# bristol_longshot_development.net
KiCad netlist of a schematic drawn in EAGLE
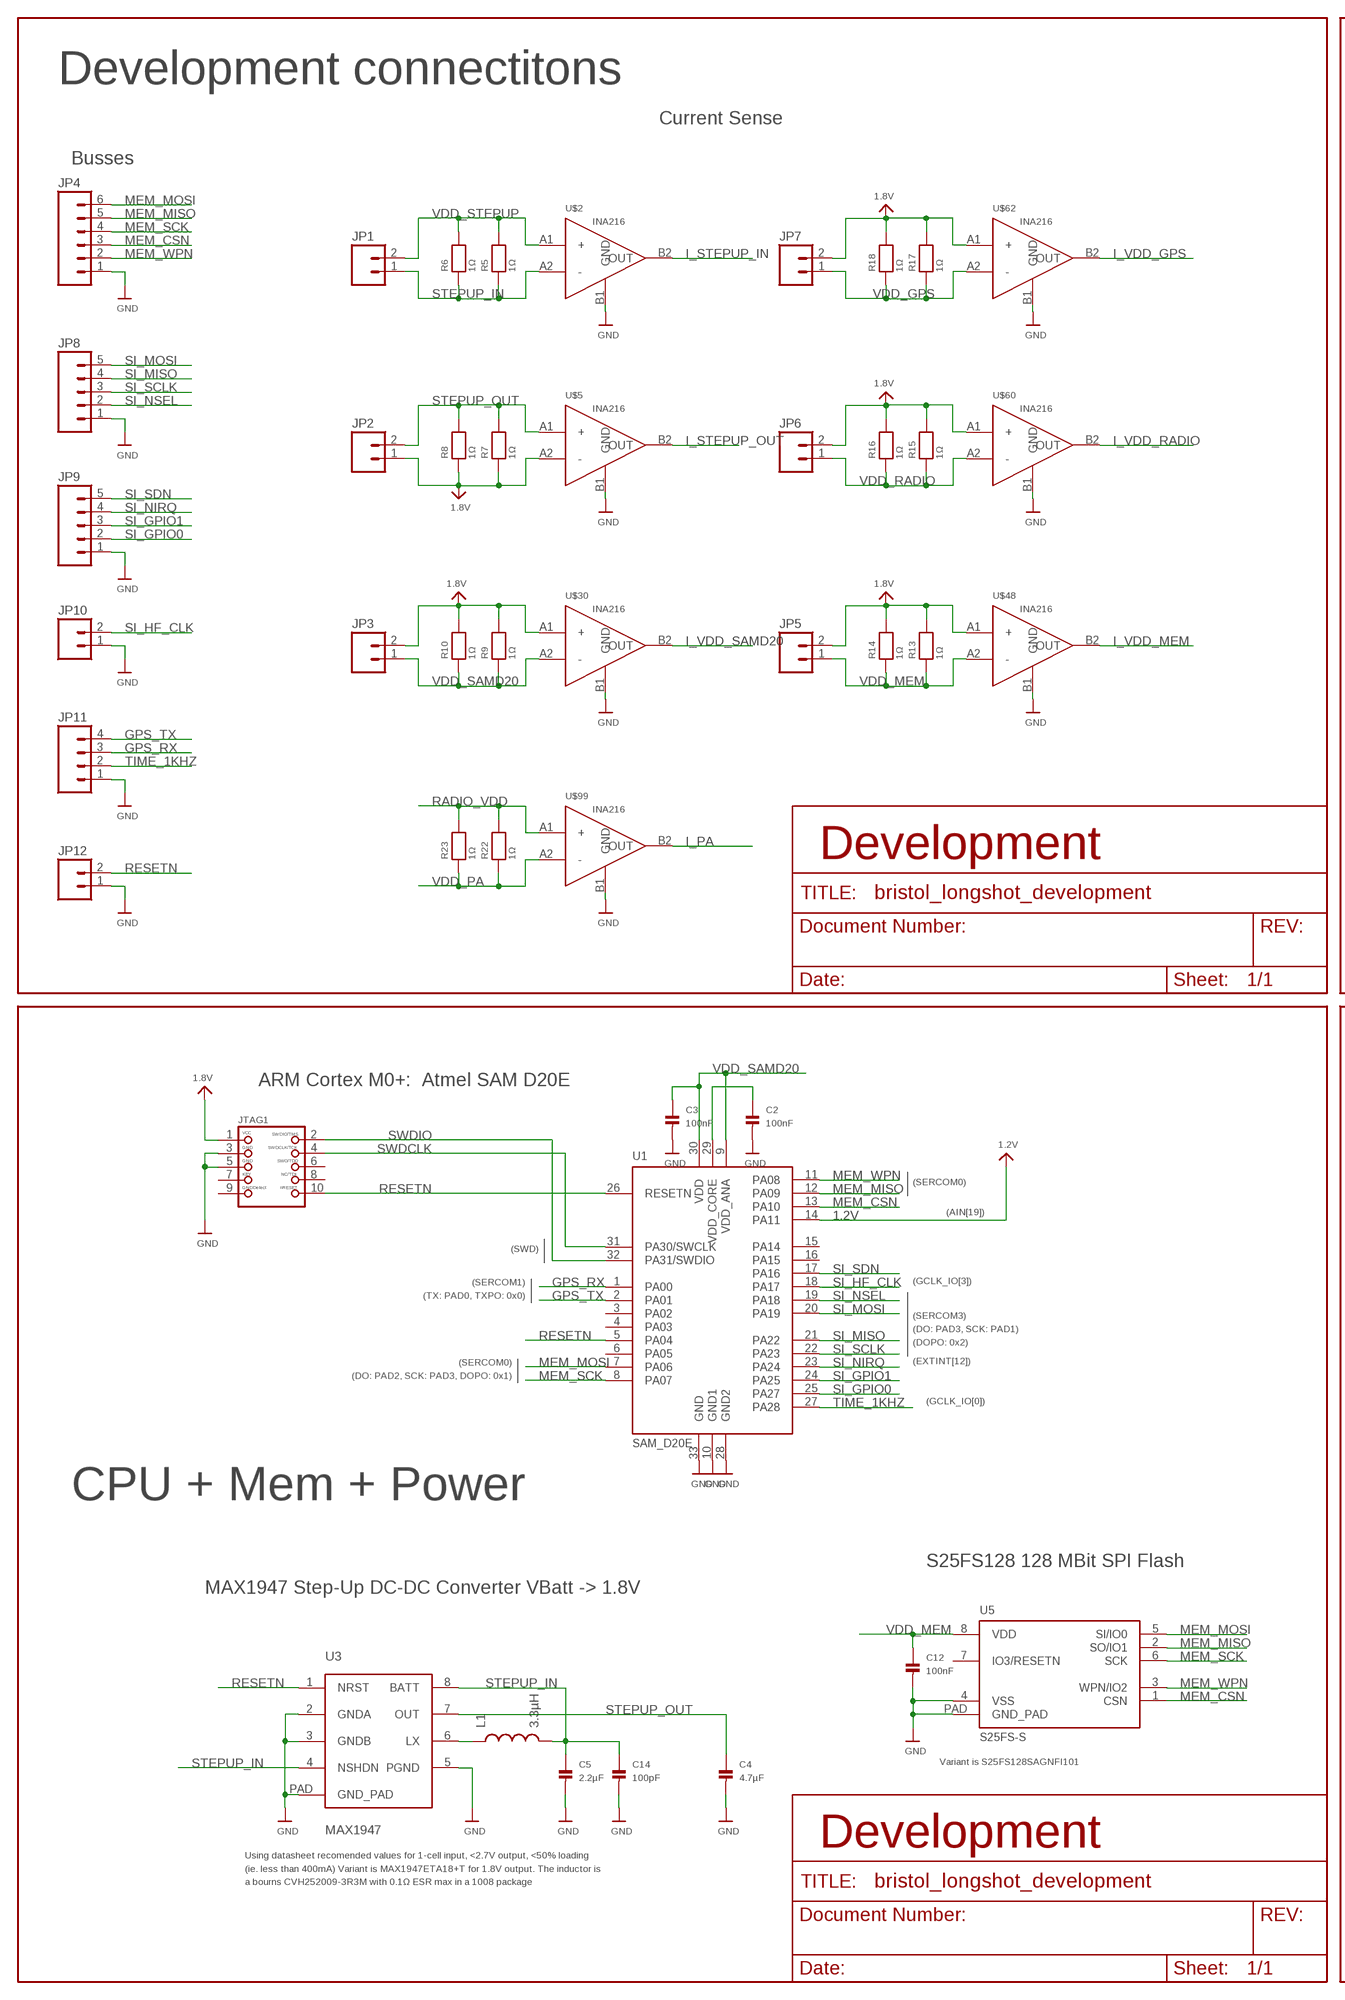
[diagram p0: schematic, sheet 1, part 1 of 2]
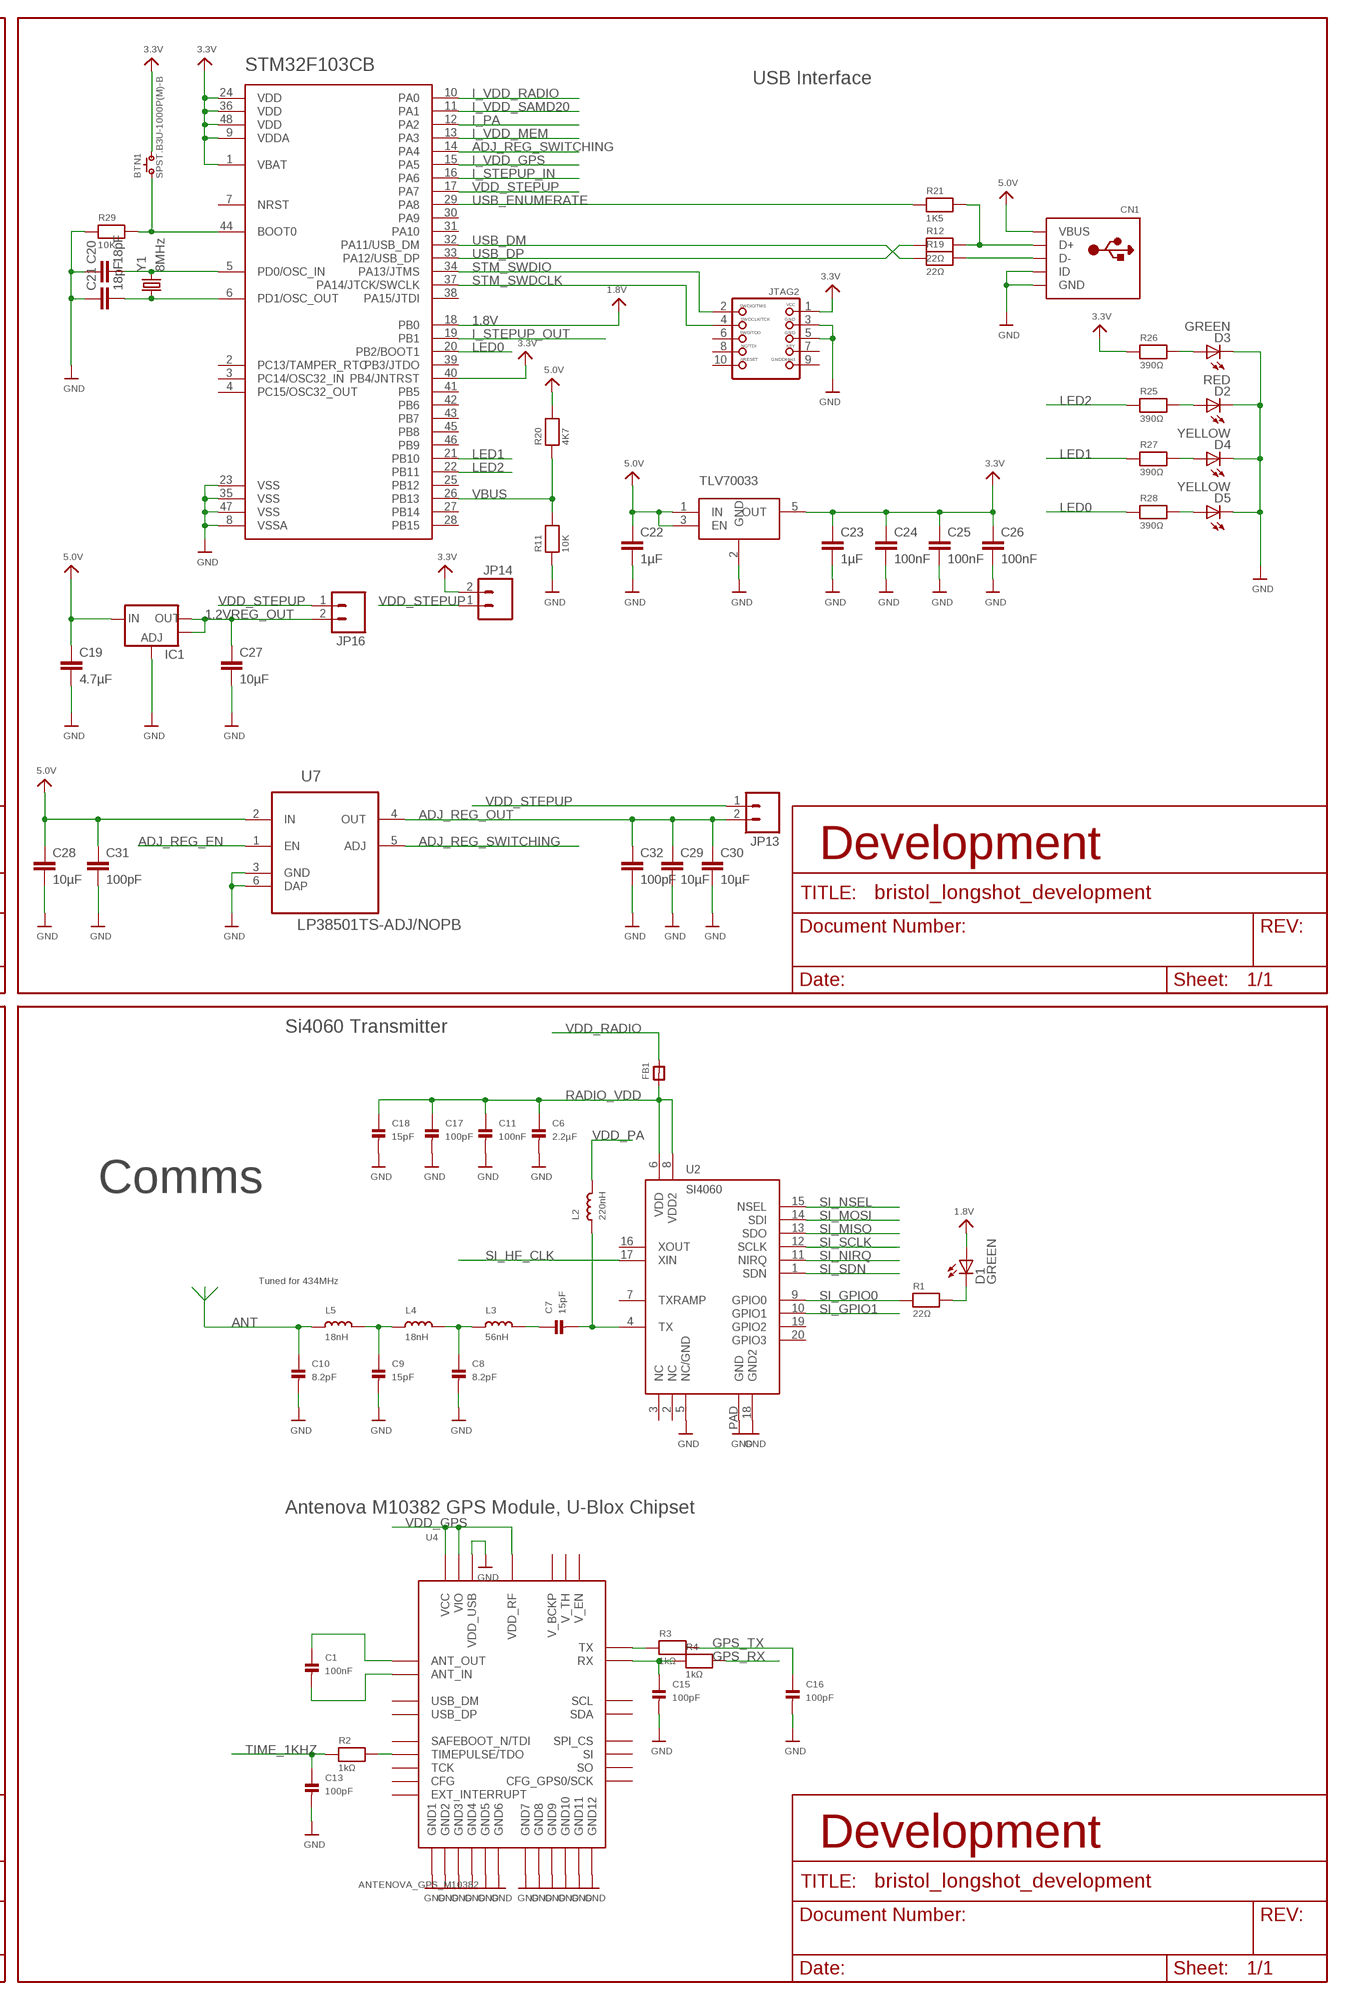
[diagram p1: schematic, sheet 1, part 2 of 2]

(export (version "E")
  (design (tool "Eeschema 10.0.6"))
  (components
    (comp (ref "BTN1")
      (value "SPST.B3U-1000P(M)-B")
      (footprint "eagle-import:B3U-1000P(M)-B")
      (libsource (lib "eagle-import") (part "SPST.B3U-1000P(M)-B"))
    )
    (comp (ref "C1")
      (value "100nF")
      (footprint "eagle-import:_0402")
      (libsource (lib "eagle-import") (part "CAP_CERAMIC_0402"))
    )
    (comp (ref "C2")
      (value "100nF")
      (footprint "eagle-import:_0402")
      (libsource (lib "eagle-import") (part "CAP_CERAMIC_0402"))
    )
    (comp (ref "C3")
      (value "100nF")
      (footprint "eagle-import:_0402")
      (libsource (lib "eagle-import") (part "CAP_CERAMIC_0402"))
    )
    (comp (ref "C4")
      (value "4.7µF")
      (footprint "eagle-import:_0402")
      (libsource (lib "eagle-import") (part "CAP_CERAMIC_0402"))
    )
    (comp (ref "C5")
      (value "2.2µF")
      (footprint "eagle-import:_0402")
      (libsource (lib "eagle-import") (part "CAP_CERAMIC_0402"))
    )
    (comp (ref "C6")
      (value "2.2µF")
      (footprint "eagle-import:_0402")
      (libsource (lib "eagle-import") (part "CAP_CERAMIC_0402"))
    )
    (comp (ref "C7")
      (value "15pF")
      (footprint "eagle-import:_0402")
      (libsource (lib "eagle-import") (part "CAP_CERAMIC_0402"))
    )
    (comp (ref "C8")
      (value "8.2pF")
      (footprint "eagle-import:_0402")
      (libsource (lib "eagle-import") (part "CAP_CERAMIC_0402"))
    )
    (comp (ref "C9")
      (value "15pF")
      (footprint "eagle-import:_0402")
      (libsource (lib "eagle-import") (part "CAP_CERAMIC_0402"))
    )
    (comp (ref "C10")
      (value "8.2pF")
      (footprint "eagle-import:_0402")
      (libsource (lib "eagle-import") (part "CAP_CERAMIC_0402"))
    )
    (comp (ref "C11")
      (value "100nF")
      (footprint "eagle-import:_0402")
      (libsource (lib "eagle-import") (part "CAP_CERAMIC_0402"))
    )
    (comp (ref "C12")
      (value "100nF")
      (footprint "eagle-import:_0402")
      (libsource (lib "eagle-import") (part "CAP_CERAMIC_0402"))
    )
    (comp (ref "C13")
      (value "100pF")
      (footprint "eagle-import:_0402")
      (libsource (lib "eagle-import") (part "CAP_CERAMIC_0402"))
    )
    (comp (ref "C14")
      (value "100pF")
      (footprint "eagle-import:_0402")
      (libsource (lib "eagle-import") (part "CAP_CERAMIC_0402"))
    )
    (comp (ref "C15")
      (value "100pF")
      (footprint "eagle-import:_0402")
      (libsource (lib "eagle-import") (part "CAP_CERAMIC_0402"))
    )
    (comp (ref "C16")
      (value "100pF")
      (footprint "eagle-import:_0402")
      (libsource (lib "eagle-import") (part "CAP_CERAMIC_0402"))
    )
    (comp (ref "C17")
      (value "100pF")
      (footprint "eagle-import:_0402")
      (libsource (lib "eagle-import") (part "CAP_CERAMIC_0402"))
    )
    (comp (ref "C18")
      (value "15pF")
      (footprint "eagle-import:_0402")
      (libsource (lib "eagle-import") (part "CAP_CERAMIC_0402"))
    )
    (comp (ref "C19")
      (value "4.7µF")
      (footprint "eagle-import:C0603K")
      (libsource (lib "eagle-import") (part "C-EUC0603K"))
    )
    (comp (ref "C20")
      (value "18pF")
      (footprint "eagle-import:C0603K")
      (libsource (lib "eagle-import") (part "C-EUC0603K"))
    )
    (comp (ref "C21")
      (value "18pF")
      (footprint "eagle-import:C0603K")
      (libsource (lib "eagle-import") (part "C-EUC0603K"))
    )
    (comp (ref "C22")
      (value "1µF")
      (footprint "eagle-import:C0603K")
      (libsource (lib "eagle-import") (part "C-EUC0603K"))
    )
    (comp (ref "C23")
      (value "1µF")
      (footprint "eagle-import:C0603K")
      (libsource (lib "eagle-import") (part "C-EUC0603K"))
    )
    (comp (ref "C24")
      (value "100nF")
      (footprint "eagle-import:C0603K")
      (libsource (lib "eagle-import") (part "C-EUC0603K"))
    )
    (comp (ref "C25")
      (value "100nF")
      (footprint "eagle-import:C0603K")
      (libsource (lib "eagle-import") (part "C-EUC0603K"))
    )
    (comp (ref "C26")
      (value "100nF")
      (footprint "eagle-import:C0603K")
      (libsource (lib "eagle-import") (part "C-EUC0603K"))
    )
    (comp (ref "C27")
      (value "10µF")
      (footprint "eagle-import:C0603K")
      (libsource (lib "eagle-import") (part "C-EUC0603K"))
    )
    (comp (ref "C28")
      (value "10µF")
      (footprint "eagle-import:C0603K")
      (libsource (lib "eagle-import") (part "C-EUC0603K"))
    )
    (comp (ref "C29")
      (value "10µF")
      (footprint "eagle-import:C0603K")
      (libsource (lib "eagle-import") (part "C-EUC0603K"))
    )
    (comp (ref "C30")
      (value "10µF")
      (footprint "eagle-import:C0603K")
      (libsource (lib "eagle-import") (part "C-EUC0603K"))
    )
    (comp (ref "C31")
      (value "100pF")
      (footprint "eagle-import:C0603K")
      (libsource (lib "eagle-import") (part "C-EUC0603K"))
    )
    (comp (ref "C32")
      (value "100pF")
      (footprint "eagle-import:C0603K")
      (libsource (lib "eagle-import") (part "C-EUC0603K"))
    )
    (comp (ref "CN1")
      (value "USBMINIB")
      (footprint "eagle-import:USB-MINIB")
      (libsource (lib "eagle-import") (part "USBMINIB"))
    )
    (comp (ref "D1")
      (value "GREEN")
      (footprint "eagle-import:CHIPLED_0603")
      (libsource (lib "eagle-import") (part "LEDCHIPLED_0603"))
    )
    (comp (ref "D2")
      (value "RED")
      (footprint "eagle-import:CHIPLED_0603")
      (libsource (lib "eagle-import") (part "LEDCHIPLED_0603"))
    )
    (comp (ref "D3")
      (value "GREEN")
      (footprint "eagle-import:CHIPLED_0603")
      (libsource (lib "eagle-import") (part "LEDCHIPLED_0603"))
    )
    (comp (ref "D4")
      (value "YELLOW")
      (footprint "eagle-import:CHIPLED_0603")
      (libsource (lib "eagle-import") (part "LEDCHIPLED_0603"))
    )
    (comp (ref "D5")
      (value "YELLOW")
      (footprint "eagle-import:CHIPLED_0603")
      (libsource (lib "eagle-import") (part "LEDCHIPLED_0603"))
    )
    (comp (ref "FB1")
      (value "FERRITE_0402")
      (footprint "eagle-import:_0402")
      (libsource (lib "eagle-import") (part "FERRITE_0402"))
    )
    (comp (ref "IC1")
      (value "V_REG_LM1117SOT223")
      (footprint "eagle-import:SOT223")
      (libsource (lib "eagle-import") (part "V_REG_LM1117SOT223"))
    )
    (comp (ref "IC3")
      (value "TLV70033DCK")
      (footprint "eagle-import:SC70-5L")
      (libsource (lib "eagle-import") (part "TLV700DCK"))
    )
    (comp (ref "JP1")
      (value "M02LOCK")
      (footprint "eagle-import:1X02_LOCK")
      (libsource (lib "eagle-import") (part "M02LOCK"))
    )
    (comp (ref "JP2")
      (value "M02LOCK")
      (footprint "eagle-import:1X02_LOCK")
      (libsource (lib "eagle-import") (part "M02LOCK"))
    )
    (comp (ref "JP3")
      (value "M02LOCK")
      (footprint "eagle-import:1X02_LOCK")
      (libsource (lib "eagle-import") (part "M02LOCK"))
    )
    (comp (ref "JP4")
      (value "M06LOCK")
      (footprint "eagle-import:1X06_LOCK")
      (libsource (lib "eagle-import") (part "M06LOCK"))
    )
    (comp (ref "JP5")
      (value "M02LOCK")
      (footprint "eagle-import:1X02_LOCK")
      (libsource (lib "eagle-import") (part "M02LOCK"))
    )
    (comp (ref "JP6")
      (value "M02LOCK")
      (footprint "eagle-import:1X02_LOCK")
      (libsource (lib "eagle-import") (part "M02LOCK"))
    )
    (comp (ref "JP7")
      (value "M02LOCK")
      (footprint "eagle-import:1X02_LOCK")
      (libsource (lib "eagle-import") (part "M02LOCK"))
    )
    (comp (ref "JP8")
      (value "M05LOCK")
      (footprint "eagle-import:1X05_LOCK")
      (libsource (lib "eagle-import") (part "M05LOCK"))
    )
    (comp (ref "JP9")
      (value "M05LOCK")
      (footprint "eagle-import:1X05_LOCK")
      (libsource (lib "eagle-import") (part "M05LOCK"))
    )
    (comp (ref "JP10")
      (value "M02LOCK")
      (footprint "eagle-import:1X02_LOCK")
      (libsource (lib "eagle-import") (part "M02LOCK"))
    )
    (comp (ref "JP11")
      (value "M04LOCK")
      (footprint "eagle-import:1X04_LOCK")
      (libsource (lib "eagle-import") (part "M04LOCK"))
    )
    (comp (ref "JP12")
      (value "M02LOCK")
      (footprint "eagle-import:1X02_LOCK")
      (libsource (lib "eagle-import") (part "M02LOCK"))
    )
    (comp (ref "JP13")
      (value "M02LOCK")
      (footprint "eagle-import:1X02_LOCK")
      (libsource (lib "eagle-import") (part "M02LOCK"))
    )
    (comp (ref "JP14")
      (value "M02LOCK")
      (footprint "eagle-import:1X02_LOCK")
      (libsource (lib "eagle-import") (part "M02LOCK"))
    )
    (comp (ref "JP16")
      (value "M02LOCK")
      (footprint "eagle-import:1X02_LOCK")
      (libsource (lib "eagle-import") (part "M02LOCK"))
    )
    (comp (ref "JTAG1")
      (value "JTAG-CORTEXM3SMT")
      (footprint "eagle-import:2X05_1.27MM_SMT")
      (libsource (lib "eagle-import") (part "JTAG-CORTEXM3SMT"))
    )
    (comp (ref "JTAG2")
      (value "JTAG-CORTEXM3SMT")
      (footprint "eagle-import:2X05_1.27MM_SMT")
      (libsource (lib "eagle-import") (part "JTAG-CORTEXM3SMT"))
    )
    (comp (ref "L1")
      (value "3.3µH")
      (footprint "eagle-import:1007")
      (libsource (lib "eagle-import") (part "INDUCTOR1007"))
    )
    (comp (ref "L2")
      (value "220nH")
      (footprint "eagle-import:_0402")
      (libsource (lib "eagle-import") (part "INDUCTOR_0402"))
    )
    (comp (ref "L3")
      (value "56nH")
      (footprint "eagle-import:_0402")
      (libsource (lib "eagle-import") (part "INDUCTOR_0402"))
    )
    (comp (ref "L4")
      (value "18nH")
      (footprint "eagle-import:_0402")
      (libsource (lib "eagle-import") (part "INDUCTOR_0402"))
    )
    (comp (ref "L5")
      (value "18nH")
      (footprint "eagle-import:_0402")
      (libsource (lib "eagle-import") (part "INDUCTOR_0402"))
    )
    (comp (ref "R1")
      (value "22Ω")
      (footprint "eagle-import:_0402")
      (libsource (lib "eagle-import") (part "RESISTOR_0402"))
    )
    (comp (ref "R2")
      (value "1kΩ")
      (footprint "eagle-import:_0402")
      (libsource (lib "eagle-import") (part "RESISTOR_0402"))
    )
    (comp (ref "R3")
      (value "1kΩ")
      (footprint "eagle-import:_0402")
      (libsource (lib "eagle-import") (part "RESISTOR_0402"))
    )
    (comp (ref "R4")
      (value "1kΩ")
      (footprint "eagle-import:_0402")
      (libsource (lib "eagle-import") (part "RESISTOR_0402"))
    )
    (comp (ref "R5")
      (value "1Ω")
      (footprint "eagle-import:_0402")
      (libsource (lib "eagle-import") (part "RESISTOR_0402"))
    )
    (comp (ref "R6")
      (value "1Ω")
      (footprint "eagle-import:_0402")
      (libsource (lib "eagle-import") (part "RESISTOR_0402"))
    )
    (comp (ref "R7")
      (value "1Ω")
      (footprint "eagle-import:_0402")
      (libsource (lib "eagle-import") (part "RESISTOR_0402"))
    )
    (comp (ref "R8")
      (value "1Ω")
      (footprint "eagle-import:_0402")
      (libsource (lib "eagle-import") (part "RESISTOR_0402"))
    )
    (comp (ref "R9")
      (value "1Ω")
      (footprint "eagle-import:_0402")
      (libsource (lib "eagle-import") (part "RESISTOR_0402"))
    )
    (comp (ref "R10")
      (value "1Ω")
      (footprint "eagle-import:_0402")
      (libsource (lib "eagle-import") (part "RESISTOR_0402"))
    )
    (comp (ref "R11")
      (value "10K")
      (footprint "eagle-import:0603-MINI")
      (libsource (lib "eagle-import") (part "RESISTOR0603MINI"))
    )
    (comp (ref "R12")
      (value "22Ω")
      (footprint "eagle-import:0603-MINI")
      (libsource (lib "eagle-import") (part "RESISTOR0603MINI"))
    )
    (comp (ref "R13")
      (value "1Ω")
      (footprint "eagle-import:_0402")
      (libsource (lib "eagle-import") (part "RESISTOR_0402"))
    )
    (comp (ref "R14")
      (value "1Ω")
      (footprint "eagle-import:_0402")
      (libsource (lib "eagle-import") (part "RESISTOR_0402"))
    )
    (comp (ref "R15")
      (value "1Ω")
      (footprint "eagle-import:_0402")
      (libsource (lib "eagle-import") (part "RESISTOR_0402"))
    )
    (comp (ref "R16")
      (value "1Ω")
      (footprint "eagle-import:_0402")
      (libsource (lib "eagle-import") (part "RESISTOR_0402"))
    )
    (comp (ref "R17")
      (value "1Ω")
      (footprint "eagle-import:_0402")
      (libsource (lib "eagle-import") (part "RESISTOR_0402"))
    )
    (comp (ref "R18")
      (value "1Ω")
      (footprint "eagle-import:_0402")
      (libsource (lib "eagle-import") (part "RESISTOR_0402"))
    )
    (comp (ref "R19")
      (value "22Ω")
      (footprint "eagle-import:0603-MINI")
      (libsource (lib "eagle-import") (part "RESISTOR0603MINI"))
    )
    (comp (ref "R20")
      (value "4K7")
      (footprint "eagle-import:0603-MINI")
      (libsource (lib "eagle-import") (part "RESISTOR0603MINI"))
    )
    (comp (ref "R21")
      (value "1K5")
      (footprint "eagle-import:0603-MINI")
      (libsource (lib "eagle-import") (part "RESISTOR0603MINI"))
    )
    (comp (ref "R22")
      (value "1Ω")
      (footprint "eagle-import:_0402")
      (libsource (lib "eagle-import") (part "RESISTOR_0402"))
    )
    (comp (ref "R23")
      (value "1Ω")
      (footprint "eagle-import:_0402")
      (libsource (lib "eagle-import") (part "RESISTOR_0402"))
    )
    (comp (ref "R25")
      (value "390Ω")
      (footprint "eagle-import:0603-MINI")
      (libsource (lib "eagle-import") (part "RESISTOR0603MINI"))
    )
    (comp (ref "R26")
      (value "390Ω")
      (footprint "eagle-import:0603-MINI")
      (libsource (lib "eagle-import") (part "RESISTOR0603MINI"))
    )
    (comp (ref "R27")
      (value "390Ω")
      (footprint "eagle-import:0603-MINI")
      (libsource (lib "eagle-import") (part "RESISTOR0603MINI"))
    )
    (comp (ref "R28")
      (value "390Ω")
      (footprint "eagle-import:0603-MINI")
      (libsource (lib "eagle-import") (part "RESISTOR0603MINI"))
    )
    (comp (ref "R29")
      (value "10K")
      (footprint "eagle-import:0603-MINI")
      (libsource (lib "eagle-import") (part "RESISTOR0603MINI"))
    )
    (comp (ref "U$2")
      (value "INA216")
      (footprint "eagle-import:WCSP-4")
      (libsource (lib "eagle-import") (part "INA216"))
    )
    (comp (ref "U$5")
      (value "INA216")
      (footprint "eagle-import:WCSP-4")
      (libsource (lib "eagle-import") (part "INA216"))
    )
    (comp (ref "U$30")
      (value "INA216")
      (footprint "eagle-import:WCSP-4")
      (libsource (lib "eagle-import") (part "INA216"))
    )
    (comp (ref "U$48")
      (value "INA216")
      (footprint "eagle-import:WCSP-4")
      (libsource (lib "eagle-import") (part "INA216"))
    )
    (comp (ref "U$60")
      (value "INA216")
      (footprint "eagle-import:WCSP-4")
      (libsource (lib "eagle-import") (part "INA216"))
    )
    (comp (ref "U$62")
      (value "INA216")
      (footprint "eagle-import:WCSP-4")
      (libsource (lib "eagle-import") (part "INA216"))
    )
    (comp (ref "U$99")
      (value "INA216")
      (footprint "eagle-import:WCSP-4")
      (libsource (lib "eagle-import") (part "INA216"))
    )
    (comp (ref "U1")
      (value "SAM_D20E")
      (footprint "eagle-import:QFN32_5MM")
      (libsource (lib "eagle-import") (part "SAM_D20E"))
    )
    (comp (ref "U2")
      (value "SI4060")
      (footprint "eagle-import:QFN20")
      (libsource (lib "eagle-import") (part "SI4060"))
    )
    (comp (ref "U3")
      (value "MAX1947")
      (footprint "eagle-import:TDFN8")
      (libsource (lib "eagle-import") (part "MAX1947"))
    )
    (comp (ref "U4")
      (value "ANTENOVA_GPS_M10382")
      (footprint "eagle-import:ANTENOVA_GPS_M10382")
      (libsource (lib "eagle-import") (part "ANTENOVA_GPS_M10382"))
    )
    (comp (ref "U5")
      (value "S25FS-S")
      (footprint "eagle-import:WSON8")
      (libsource (lib "eagle-import") (part "S25FS-S"))
    )
    (comp (ref "U6")
      (value "STM32F_48PIN")
      (footprint "eagle-import:TQFP48")
      (libsource (lib "eagle-import") (part "STM32F_48PIN"))
    )
    (comp (ref "U7")
      (value "LP38501TS-ADJ/NOPB")
      (footprint "eagle-import:TO170P1435X457-6N")
      (libsource (lib "eagle-import") (part "LP38501TS-ADJ/NOPB"))
    )
    (comp (ref "Y1")
      (value "8MHz")
      (footprint "eagle-import:CRYSTAL-SMD-5X3")
      (libsource (lib "eagle-import") (part "CRYSTAL5X3"))
    )
  )
  (nets
    (net (code "1") (name "/1.2VREG_OUT") (class "Default")
      (node (ref "C27") (pin "1") (pinfunction "1_1") (pintype "passive"))
      (node (ref "IC1") (pin "2") (pinfunction "OUT_2") (pintype "output"))
      (node (ref "IC1") (pin "4") (pinfunction "OUT_4") (pintype "output"))
      (node (ref "JP16") (pin "2") (pinfunction "2_2") (pintype "passive"))
    )
    (net (code "2") (name "/ADJ_REG_EN") (class "Default")
      (node (ref "U7") (pin "1") (pinfunction "EN_1") (pintype "input"))
    )
    (net (code "3") (name "/ADJ_REG_OUT") (class "Default")
      (node (ref "C29") (pin "1") (pinfunction "1_1") (pintype "passive"))
      (node (ref "C30") (pin "1") (pinfunction "1_1") (pintype "passive"))
      (node (ref "C32") (pin "1") (pinfunction "1_1") (pintype "passive"))
      (node (ref "JP13") (pin "2") (pinfunction "2_2") (pintype "passive"))
      (node (ref "U7") (pin "4") (pinfunction "OUT_4") (pintype "output"))
    )
    (net (code "4") (name "/ADJ_REG_SWITCHING") (class "Default")
      (node (ref "U6") (pin "14") (pinfunction "PA4_14") (pintype "bidirectional"))
      (node (ref "U7") (pin "5") (pinfunction "ADJ_5") (pintype "input"))
    )
    (net (code "5") (name "/ANT") (class "Default")
      (node (ref "C10") (pin "1") (pinfunction "P$1_1") (pintype "passive"))
      (node (ref "L5") (pin "1") (pinfunction "1_1") (pintype "passive"))
    )
    (net (code "6") (name "/GPS_RX") (class "Default")
      (node (ref "JP11") (pin "3") (pinfunction "3_3") (pintype "passive"))
      (node (ref "R4") (pin "2") (pinfunction "2_2") (pintype "passive"))
      (node (ref "U1") (pin "1") (pinfunction "PA00_1") (pintype "bidirectional"))
    )
    (net (code "7") (name "/GPS_TX") (class "Default")
      (node (ref "C16") (pin "1") (pinfunction "P$1_1") (pintype "passive"))
      (node (ref "JP11") (pin "4") (pinfunction "4_4") (pintype "passive"))
      (node (ref "R3") (pin "2") (pinfunction "2_2") (pintype "passive"))
      (node (ref "U1") (pin "2") (pinfunction "PA01_2") (pintype "bidirectional"))
    )
    (net (code "8") (name "/I_PA") (class "Default")
      (node (ref "U$99") (pin "B2") (pinfunction "OUT_B2") (pintype "bidirectional"))
      (node (ref "U6") (pin "12") (pinfunction "PA2_12") (pintype "bidirectional"))
    )
    (net (code "9") (name "/I_STEPUP_IN") (class "Default")
      (node (ref "U$2") (pin "B2") (pinfunction "OUT_B2") (pintype "bidirectional"))
      (node (ref "U6") (pin "16") (pinfunction "PA6_16") (pintype "bidirectional"))
    )
    (net (code "10") (name "/I_STEPUP_OUT") (class "Default")
      (node (ref "U$5") (pin "B2") (pinfunction "OUT_B2") (pintype "bidirectional"))
      (node (ref "U6") (pin "19") (pinfunction "PB1_19") (pintype "bidirectional"))
    )
    (net (code "11") (name "/I_VDD_GPS") (class "Default")
      (node (ref "U$62") (pin "B2") (pinfunction "OUT_B2") (pintype "bidirectional"))
      (node (ref "U6") (pin "15") (pinfunction "PA5_15") (pintype "bidirectional"))
    )
    (net (code "12") (name "/I_VDD_MEM") (class "Default")
      (node (ref "U$48") (pin "B2") (pinfunction "OUT_B2") (pintype "bidirectional"))
      (node (ref "U6") (pin "13") (pinfunction "PA3_13") (pintype "bidirectional"))
    )
    (net (code "13") (name "/I_VDD_RADIO") (class "Default")
      (node (ref "U$60") (pin "B2") (pinfunction "OUT_B2") (pintype "bidirectional"))
      (node (ref "U6") (pin "10") (pinfunction "PA0_10") (pintype "bidirectional"))
    )
    (net (code "14") (name "/I_VDD_SAMD20") (class "Default")
      (node (ref "U$30") (pin "B2") (pinfunction "OUT_B2") (pintype "bidirectional"))
      (node (ref "U6") (pin "11") (pinfunction "PA1_11") (pintype "bidirectional"))
    )
    (net (code "15") (name "/LED0") (class "Default")
      (node (ref "R28") (pin "1") (pinfunction "1_1") (pintype "passive"))
      (node (ref "U6") (pin "20") (pinfunction "PB2/BOOT1_20") (pintype "bidirectional"))
    )
    (net (code "16") (name "/LED1") (class "Default")
      (node (ref "R27") (pin "1") (pinfunction "1_1") (pintype "passive"))
      (node (ref "U6") (pin "21") (pinfunction "PB10_21") (pintype "bidirectional"))
    )
    (net (code "17") (name "/LED2") (class "Default")
      (node (ref "R25") (pin "1") (pinfunction "1_1") (pintype "passive"))
      (node (ref "U6") (pin "22") (pinfunction "PB11_22") (pintype "bidirectional"))
    )
    (net (code "18") (name "/MEM_CSN") (class "Default")
      (node (ref "JP4") (pin "3") (pinfunction "3_3") (pintype "passive"))
      (node (ref "U1") (pin "13") (pinfunction "PA10_13") (pintype "bidirectional"))
      (node (ref "U5") (pin "1") (pinfunction "CSN_1") (pintype "input"))
    )
    (net (code "19") (name "/MEM_MISO") (class "Default")
      (node (ref "JP4") (pin "5") (pinfunction "5_5") (pintype "passive"))
      (node (ref "U1") (pin "12") (pinfunction "PA09_12") (pintype "bidirectional"))
      (node (ref "U5") (pin "2") (pinfunction "SO/IO1_2") (pintype "output"))
    )
    (net (code "20") (name "/MEM_MOSI") (class "Default")
      (node (ref "JP4") (pin "6") (pinfunction "6_6") (pintype "passive"))
      (node (ref "U1") (pin "7") (pinfunction "PA06_7") (pintype "bidirectional"))
      (node (ref "U5") (pin "5") (pinfunction "SI/IO0_5") (pintype "bidirectional"))
    )
    (net (code "21") (name "/MEM_SCK") (class "Default")
      (node (ref "JP4") (pin "4") (pinfunction "4_4") (pintype "passive"))
      (node (ref "U1") (pin "8") (pinfunction "PA07_8") (pintype "bidirectional"))
      (node (ref "U5") (pin "6") (pinfunction "SCK_6") (pintype "input"))
    )
    (net (code "22") (name "/MEM_WPN") (class "Default")
      (node (ref "JP4") (pin "2") (pinfunction "2_2") (pintype "passive"))
      (node (ref "U1") (pin "11") (pinfunction "PA08_11") (pintype "bidirectional"))
      (node (ref "U5") (pin "3") (pinfunction "WPN/IO2_3") (pintype "output"))
    )
    (net (code "23") (name "/RADIO_VDD") (class "Default")
      (node (ref "C11") (pin "1") (pinfunction "P$1_1") (pintype "passive"))
      (node (ref "C17") (pin "1") (pinfunction "P$1_1") (pintype "passive"))
      (node (ref "C18") (pin "1") (pinfunction "P$1_1") (pintype "passive"))
      (node (ref "C6") (pin "1") (pinfunction "P$1_1") (pintype "passive"))
      (node (ref "FB1") (pin "1") (pinfunction "P$1_1") (pintype "passive"))
      (node (ref "R22") (pin "2") (pinfunction "2_2") (pintype "passive"))
      (node (ref "R23") (pin "2") (pinfunction "2_2") (pintype "passive"))
      (node (ref "U$99") (pin "A1") (pinfunction "+_A1") (pintype "bidirectional"))
      (node (ref "U2") (pin "6") (pinfunction "VDD_6") (pintype "power_in"))
      (node (ref "U2") (pin "8") (pinfunction "VDD2_8") (pintype "power_in"))
    )
    (net (code "24") (name "/RESETN") (class "Default")
      (node (ref "JP12") (pin "2") (pinfunction "2_2") (pintype "passive"))
      (node (ref "JTAG1") (pin "10") (pinfunction "10_10") (pintype "passive"))
      (node (ref "U1") (pin "26") (pinfunction "RESETN_26") (pintype "input"))
      (node (ref "U1") (pin "5") (pinfunction "PA04_5") (pintype "bidirectional"))
      (node (ref "U3") (pin "1") (pinfunction "NRST_1") (pintype "bidirectional"))
    )
    (net (code "25") (name "/SI_GPIO0") (class "Default")
      (node (ref "JP9") (pin "2") (pinfunction "2_2") (pintype "passive"))
      (node (ref "R1") (pin "1") (pinfunction "1_1") (pintype "passive"))
      (node (ref "U1") (pin "25") (pinfunction "PA27_25") (pintype "bidirectional"))
      (node (ref "U2") (pin "9") (pinfunction "GPIO0_9") (pintype "bidirectional"))
    )
    (net (code "26") (name "/SI_GPIO1") (class "Default")
      (node (ref "JP9") (pin "3") (pinfunction "3_3") (pintype "passive"))
      (node (ref "U1") (pin "24") (pinfunction "PA25_24") (pintype "bidirectional"))
      (node (ref "U2") (pin "10") (pinfunction "GPIO1_10") (pintype "bidirectional"))
    )
    (net (code "27") (name "/SI_HF_CLK") (class "Default")
      (node (ref "JP10") (pin "2") (pinfunction "2_2") (pintype "passive"))
      (node (ref "U1") (pin "18") (pinfunction "PA17_18") (pintype "bidirectional"))
      (node (ref "U2") (pin "17") (pinfunction "XIN_17") (pintype "input"))
    )
    (net (code "28") (name "/SI_MISO") (class "Default")
      (node (ref "JP8") (pin "4") (pinfunction "4_4") (pintype "passive"))
      (node (ref "U1") (pin "21") (pinfunction "PA22_21") (pintype "bidirectional"))
      (node (ref "U2") (pin "13") (pinfunction "SDO_13") (pintype "output"))
    )
    (net (code "29") (name "/SI_MOSI") (class "Default")
      (node (ref "JP8") (pin "5") (pinfunction "5_5") (pintype "passive"))
      (node (ref "U1") (pin "20") (pinfunction "PA19_20") (pintype "bidirectional"))
      (node (ref "U2") (pin "14") (pinfunction "SDI_14") (pintype "bidirectional"))
    )
    (net (code "30") (name "/SI_NIRQ") (class "Default")
      (node (ref "JP9") (pin "4") (pinfunction "4_4") (pintype "passive"))
      (node (ref "U1") (pin "23") (pinfunction "PA24_23") (pintype "bidirectional"))
      (node (ref "U2") (pin "11") (pinfunction "NIRQ_11") (pintype "output"))
    )
    (net (code "31") (name "/SI_NSEL") (class "Default")
      (node (ref "JP8") (pin "2") (pinfunction "2_2") (pintype "passive"))
      (node (ref "U1") (pin "19") (pinfunction "PA18_19") (pintype "bidirectional"))
      (node (ref "U2") (pin "15") (pinfunction "NSEL_15") (pintype "input"))
    )
    (net (code "32") (name "/SI_SCLK") (class "Default")
      (node (ref "JP8") (pin "3") (pinfunction "3_3") (pintype "passive"))
      (node (ref "U1") (pin "22") (pinfunction "PA23_22") (pintype "bidirectional"))
      (node (ref "U2") (pin "12") (pinfunction "SCLK_12") (pintype "input"))
    )
    (net (code "33") (name "/SI_SDN") (class "Default")
      (node (ref "JP9") (pin "5") (pinfunction "5_5") (pintype "passive"))
      (node (ref "U1") (pin "17") (pinfunction "PA16_17") (pintype "bidirectional"))
      (node (ref "U2") (pin "1") (pinfunction "SDN_1") (pintype "input"))
    )
    (net (code "34") (name "/STEPUP_IN") (class "Default")
      (node (ref "C14") (pin "1") (pinfunction "P$1_1") (pintype "passive"))
      (node (ref "C5") (pin "1") (pinfunction "P$1_1") (pintype "passive"))
      (node (ref "JP1") (pin "1") (pinfunction "1_1") (pintype "passive"))
      (node (ref "L1") (pin "2") (pinfunction "2_2") (pintype "passive"))
      (node (ref "R5") (pin "1") (pinfunction "1_1") (pintype "passive"))
      (node (ref "R6") (pin "1") (pinfunction "1_1") (pintype "passive"))
      (node (ref "U$2") (pin "A2") (pinfunction "-_A2") (pintype "bidirectional"))
      (node (ref "U3") (pin "4") (pinfunction "NSHDN_4") (pintype "bidirectional"))
      (node (ref "U3") (pin "8") (pinfunction "BATT_8") (pintype "bidirectional"))
    )
    (net (code "35") (name "/STEPUP_OUT") (class "Default")
      (node (ref "C4") (pin "1") (pinfunction "P$1_1") (pintype "passive"))
      (node (ref "JP2") (pin "2") (pinfunction "2_2") (pintype "passive"))
      (node (ref "R7") (pin "2") (pinfunction "2_2") (pintype "passive"))
      (node (ref "R8") (pin "2") (pinfunction "2_2") (pintype "passive"))
      (node (ref "U$5") (pin "A1") (pinfunction "+_A1") (pintype "bidirectional"))
      (node (ref "U3") (pin "7") (pinfunction "OUT_7") (pintype "bidirectional"))
    )
    (net (code "36") (name "/STM_SWDCLK") (class "Default")
      (node (ref "JTAG2") (pin "4") (pinfunction "4_4") (pintype "passive"))
      (node (ref "U6") (pin "37") (pinfunction "PA14/JTCK/SWCLK_37") (pintype "bidirectional"))
    )
    (net (code "37") (name "/STM_SWDIO") (class "Default")
      (node (ref "JTAG2") (pin "2") (pinfunction "2_2") (pintype "passive"))
      (node (ref "U6") (pin "34") (pinfunction "PA13/JTMS_34") (pintype "bidirectional"))
    )
    (net (code "38") (name "/SWDCLK") (class "Default")
      (node (ref "JTAG1") (pin "4") (pinfunction "4_4") (pintype "passive"))
      (node (ref "U1") (pin "31") (pinfunction "PA30/SWCLK_31") (pintype "bidirectional"))
    )
    (net (code "39") (name "/SWDIO") (class "Default")
      (node (ref "JTAG1") (pin "2") (pinfunction "2_2") (pintype "passive"))
      (node (ref "U1") (pin "32") (pinfunction "PA31/SWDIO_32") (pintype "bidirectional"))
    )
    (net (code "40") (name "/TIME_1KHZ") (class "Default")
      (node (ref "C13") (pin "1") (pinfunction "P$1_1") (pintype "passive"))
      (node (ref "JP11") (pin "2") (pinfunction "2_2") (pintype "passive"))
      (node (ref "R2") (pin "1") (pinfunction "1_1") (pintype "passive"))
      (node (ref "U1") (pin "27") (pinfunction "PA28_27") (pintype "bidirectional"))
    )
    (net (code "41") (name "/USB_DM") (class "Default")
      (node (ref "R19") (pin "1") (pinfunction "1_1") (pintype "passive"))
      (node (ref "U6") (pin "32") (pinfunction "PA11/USB_DM_32") (pintype "bidirectional"))
    )
    (net (code "42") (name "/USB_DP") (class "Default")
      (node (ref "R12") (pin "1") (pinfunction "1_1") (pintype "passive"))
      (node (ref "U6") (pin "33") (pinfunction "PA12/USB_DP_33") (pintype "bidirectional"))
    )
    (net (code "43") (name "/USB_ENUMERATE") (class "Default")
      (node (ref "R21") (pin "1") (pinfunction "1_1") (pintype "passive"))
      (node (ref "U6") (pin "29") (pinfunction "PA8_29") (pintype "bidirectional"))
    )
    (net (code "44") (name "/VBUS") (class "Default")
      (node (ref "R11") (pin "2") (pinfunction "2_2") (pintype "passive"))
      (node (ref "R20") (pin "1") (pinfunction "1_1") (pintype "passive"))
      (node (ref "U6") (pin "26") (pinfunction "PB13_26") (pintype "bidirectional"))
    )
    (net (code "45") (name "/VDD_GPS") (class "Default")
      (node (ref "JP7") (pin "1") (pinfunction "1_1") (pintype "passive"))
      (node (ref "R17") (pin "1") (pinfunction "1_1") (pintype "passive"))
      (node (ref "R18") (pin "1") (pinfunction "1_1") (pintype "passive"))
      (node (ref "U$62") (pin "A2") (pinfunction "-_A2") (pintype "bidirectional"))
      (node (ref "U4") (pin "25_VDD_RF") (pinfunction "VDD_RF_25_VDD_RF") (pintype "power_in"))
      (node (ref "U4") (pin "27_VCC") (pinfunction "VCC_27_VCC") (pintype "power_in"))
      (node (ref "U4") (pin "5_VIO") (pinfunction "VIO_5_VIO") (pintype "bidirectional"))
    )
    (net (code "46") (name "/VDD_MEM") (class "Default")
      (node (ref "C12") (pin "1") (pinfunction "P$1_1") (pintype "passive"))
      (node (ref "JP5") (pin "1") (pinfunction "1_1") (pintype "passive"))
      (node (ref "R13") (pin "1") (pinfunction "1_1") (pintype "passive"))
      (node (ref "R14") (pin "1") (pinfunction "1_1") (pintype "passive"))
      (node (ref "U$48") (pin "A2") (pinfunction "-_A2") (pintype "bidirectional"))
      (node (ref "U5") (pin "8") (pinfunction "VDD_8") (pintype "power_in"))
    )
    (net (code "47") (name "/VDD_PA") (class "Default")
      (node (ref "L2") (pin "2") (pinfunction "2_2") (pintype "passive"))
      (node (ref "R22") (pin "1") (pinfunction "1_1") (pintype "passive"))
      (node (ref "R23") (pin "1") (pinfunction "1_1") (pintype "passive"))
      (node (ref "U$99") (pin "A2") (pinfunction "-_A2") (pintype "bidirectional"))
    )
    (net (code "48") (name "/VDD_RADIO") (class "Default")
      (node (ref "FB1") (pin "2") (pinfunction "P$2_2") (pintype "passive"))
      (node (ref "JP6") (pin "1") (pinfunction "1_1") (pintype "passive"))
      (node (ref "R15") (pin "1") (pinfunction "1_1") (pintype "passive"))
      (node (ref "R16") (pin "1") (pinfunction "1_1") (pintype "passive"))
      (node (ref "U$60") (pin "A2") (pinfunction "-_A2") (pintype "bidirectional"))
    )
    (net (code "49") (name "/VDD_SAMD20") (class "Default")
      (node (ref "C3") (pin "1") (pinfunction "P$1_1") (pintype "passive"))
      (node (ref "JP3") (pin "1") (pinfunction "1_1") (pintype "passive"))
      (node (ref "R10") (pin "1") (pinfunction "1_1") (pintype "passive"))
      (node (ref "R9") (pin "1") (pinfunction "1_1") (pintype "passive"))
      (node (ref "U$30") (pin "A2") (pinfunction "-_A2") (pintype "bidirectional"))
      (node (ref "U1") (pin "30") (pinfunction "VDD_30") (pintype "power_in"))
      (node (ref "U1") (pin "9") (pinfunction "VDD_ANA_9") (pintype "power_in"))
    )
    (net (code "50") (name "/VDD_STEPUP") (class "Default")
      (node (ref "JP1") (pin "2") (pinfunction "2_2") (pintype "passive"))
      (node (ref "JP13") (pin "1") (pinfunction "1_1") (pintype "passive"))
      (node (ref "JP14") (pin "1") (pinfunction "1_1") (pintype "passive"))
      (node (ref "JP16") (pin "1") (pinfunction "1_1") (pintype "passive"))
      (node (ref "R5") (pin "2") (pinfunction "2_2") (pintype "passive"))
      (node (ref "R6") (pin "2") (pinfunction "2_2") (pintype "passive"))
      (node (ref "U$2") (pin "A1") (pinfunction "+_A1") (pintype "bidirectional"))
      (node (ref "U6") (pin "17") (pinfunction "PA7_17") (pintype "bidirectional"))
    )
    (net (code "51") (name "1.2V") (class "Default")
      (node (ref "U1") (pin "14") (pinfunction "PA11_14") (pintype "bidirectional"))
    )
    (net (code "52") (name "1.8V") (class "Default")
      (node (ref "D1") (pin "A") (pinfunction "A_A") (pintype "passive"))
      (node (ref "JP2") (pin "1") (pinfunction "1_1") (pintype "passive"))
      (node (ref "JP3") (pin "2") (pinfunction "2_2") (pintype "passive"))
      (node (ref "JP5") (pin "2") (pinfunction "2_2") (pintype "passive"))
      (node (ref "JP6") (pin "2") (pinfunction "2_2") (pintype "passive"))
      (node (ref "JP7") (pin "2") (pinfunction "2_2") (pintype "passive"))
      (node (ref "JTAG1") (pin "1") (pinfunction "1_1") (pintype "passive"))
      (node (ref "R10") (pin "2") (pinfunction "2_2") (pintype "passive"))
      (node (ref "R13") (pin "2") (pinfunction "2_2") (pintype "passive"))
      (node (ref "R14") (pin "2") (pinfunction "2_2") (pintype "passive"))
      (node (ref "R15") (pin "2") (pinfunction "2_2") (pintype "passive"))
      (node (ref "R16") (pin "2") (pinfunction "2_2") (pintype "passive"))
      (node (ref "R17") (pin "2") (pinfunction "2_2") (pintype "passive"))
      (node (ref "R18") (pin "2") (pinfunction "2_2") (pintype "passive"))
      (node (ref "R7") (pin "1") (pinfunction "1_1") (pintype "passive"))
      (node (ref "R8") (pin "1") (pinfunction "1_1") (pintype "passive"))
      (node (ref "R9") (pin "2") (pinfunction "2_2") (pintype "passive"))
      (node (ref "U$30") (pin "A1") (pinfunction "+_A1") (pintype "bidirectional"))
      (node (ref "U$48") (pin "A1") (pinfunction "+_A1") (pintype "bidirectional"))
      (node (ref "U$5") (pin "A2") (pinfunction "-_A2") (pintype "bidirectional"))
      (node (ref "U$60") (pin "A1") (pinfunction "+_A1") (pintype "bidirectional"))
      (node (ref "U$62") (pin "A1") (pinfunction "+_A1") (pintype "bidirectional"))
      (node (ref "U6") (pin "18") (pinfunction "PB0_18") (pintype "bidirectional"))
    )
    (net (code "53") (name "3.3V") (class "Default")
      (node (ref "BTN1") (pin "2") (pinfunction "2_2") (pintype "bidirectional"))
      (node (ref "C23") (pin "1") (pinfunction "1_1") (pintype "passive"))
      (node (ref "C24") (pin "1") (pinfunction "1_1") (pintype "passive"))
      (node (ref "C25") (pin "1") (pinfunction "1_1") (pintype "passive"))
      (node (ref "C26") (pin "1") (pinfunction "1_1") (pintype "passive"))
      (node (ref "IC3") (pin "5") (pinfunction "OUT_5") (pintype "bidirectional"))
      (node (ref "JP14") (pin "2") (pinfunction "2_2") (pintype "passive"))
      (node (ref "JTAG2") (pin "1") (pinfunction "1_1") (pintype "passive"))
      (node (ref "R26") (pin "1") (pinfunction "1_1") (pintype "passive"))
      (node (ref "U6") (pin "1") (pinfunction "VBAT_1") (pintype "bidirectional"))
      (node (ref "U6") (pin "24") (pinfunction "VDD_24") (pintype "bidirectional"))
      (node (ref "U6") (pin "36") (pinfunction "VDD_36") (pintype "bidirectional"))
      (node (ref "U6") (pin "40") (pinfunction "PB4/JNTRST_40") (pintype "bidirectional"))
      (node (ref "U6") (pin "48") (pinfunction "VDD_48") (pintype "bidirectional"))
      (node (ref "U6") (pin "9") (pinfunction "VDDA_9") (pintype "bidirectional"))
    )
    (net (code "54") (name "5.0V") (class "Default")
      (node (ref "C19") (pin "1") (pinfunction "1_1") (pintype "passive"))
      (node (ref "C22") (pin "1") (pinfunction "1_1") (pintype "passive"))
      (node (ref "C28") (pin "1") (pinfunction "1_1") (pintype "passive"))
      (node (ref "C31") (pin "1") (pinfunction "1_1") (pintype "passive"))
      (node (ref "CN1") (pin "VBUS") (pinfunction "VBUS_VBUS") (pintype "power_in"))
      (node (ref "IC1") (pin "3") (pinfunction "IN_3") (pintype "input"))
      (node (ref "IC3") (pin "1") (pinfunction "IN_1") (pintype "bidirectional"))
      (node (ref "IC3") (pin "3") (pinfunction "EN_3") (pintype "bidirectional"))
      (node (ref "R20") (pin "2") (pinfunction "2_2") (pintype "passive"))
      (node (ref "U7") (pin "2") (pinfunction "IN_2") (pintype "power_in"))
    )
    (net (code "55") (name "GND") (class "Default")
      (node (ref "C10") (pin "2") (pinfunction "P$2_2") (pintype "passive"))
      (node (ref "C11") (pin "2") (pinfunction "P$2_2") (pintype "passive"))
      (node (ref "C12") (pin "2") (pinfunction "P$2_2") (pintype "passive"))
      (node (ref "C13") (pin "2") (pinfunction "P$2_2") (pintype "passive"))
      (node (ref "C14") (pin "2") (pinfunction "P$2_2") (pintype "passive"))
      (node (ref "C15") (pin "2") (pinfunction "P$2_2") (pintype "passive"))
      (node (ref "C16") (pin "2") (pinfunction "P$2_2") (pintype "passive"))
      (node (ref "C17") (pin "2") (pinfunction "P$2_2") (pintype "passive"))
      (node (ref "C18") (pin "2") (pinfunction "P$2_2") (pintype "passive"))
      (node (ref "C19") (pin "2") (pinfunction "2_2") (pintype "passive"))
      (node (ref "C2") (pin "2") (pinfunction "P$2_2") (pintype "passive"))
      (node (ref "C20") (pin "1") (pinfunction "1_1") (pintype "passive"))
      (node (ref "C21") (pin "1") (pinfunction "1_1") (pintype "passive"))
      (node (ref "C22") (pin "2") (pinfunction "2_2") (pintype "passive"))
      (node (ref "C23") (pin "2") (pinfunction "2_2") (pintype "passive"))
      (node (ref "C24") (pin "2") (pinfunction "2_2") (pintype "passive"))
      (node (ref "C25") (pin "2") (pinfunction "2_2") (pintype "passive"))
      (node (ref "C26") (pin "2") (pinfunction "2_2") (pintype "passive"))
      (node (ref "C27") (pin "2") (pinfunction "2_2") (pintype "passive"))
      (node (ref "C28") (pin "2") (pinfunction "2_2") (pintype "passive"))
      (node (ref "C29") (pin "2") (pinfunction "2_2") (pintype "passive"))
      (node (ref "C3") (pin "2") (pinfunction "P$2_2") (pintype "passive"))
      (node (ref "C30") (pin "2") (pinfunction "2_2") (pintype "passive"))
      (node (ref "C31") (pin "2") (pinfunction "2_2") (pintype "passive"))
      (node (ref "C32") (pin "2") (pinfunction "2_2") (pintype "passive"))
      (node (ref "C4") (pin "2") (pinfunction "P$2_2") (pintype "passive"))
      (node (ref "C5") (pin "2") (pinfunction "P$2_2") (pintype "passive"))
      (node (ref "C6") (pin "2") (pinfunction "P$2_2") (pintype "passive"))
      (node (ref "C8") (pin "2") (pinfunction "P$2_2") (pintype "passive"))
      (node (ref "C9") (pin "2") (pinfunction "P$2_2") (pintype "passive"))
      (node (ref "CN1") (pin "GND") (pinfunction "GND_GND") (pintype "power_in"))
      (node (ref "CN1") (pin "ID") (pinfunction "ID_ID") (pintype "bidirectional"))
      (node (ref "D2") (pin "C") (pinfunction "C_C") (pintype "passive"))
      (node (ref "D3") (pin "C") (pinfunction "C_C") (pintype "passive"))
      (node (ref "D4") (pin "C") (pinfunction "C_C") (pintype "passive"))
      (node (ref "D5") (pin "C") (pinfunction "C_C") (pintype "passive"))
      (node (ref "IC1") (pin "1") (pinfunction "ADJ_1") (pintype "input"))
      (node (ref "IC3") (pin "2") (pinfunction "GND_2") (pintype "bidirectional"))
      (node (ref "JP10") (pin "1") (pinfunction "1_1") (pintype "passive"))
      (node (ref "JP11") (pin "1") (pinfunction "1_1") (pintype "passive"))
      (node (ref "JP12") (pin "1") (pinfunction "1_1") (pintype "passive"))
      (node (ref "JP4") (pin "1") (pinfunction "1_1") (pintype "passive"))
      (node (ref "JP8") (pin "1") (pinfunction "1_1") (pintype "passive"))
      (node (ref "JP9") (pin "1") (pinfunction "1_1") (pintype "passive"))
      (node (ref "JTAG1") (pin "3") (pinfunction "3_3") (pintype "passive"))
      (node (ref "JTAG1") (pin "5") (pinfunction "5_5") (pintype "passive"))
      (node (ref "JTAG2") (pin "3") (pinfunction "3_3") (pintype "passive"))
      (node (ref "JTAG2") (pin "5") (pinfunction "5_5") (pintype "passive"))
      (node (ref "R11") (pin "1") (pinfunction "1_1") (pintype "passive"))
      (node (ref "R29") (pin "1") (pinfunction "1_1") (pintype "passive"))
      (node (ref "U$2") (pin "B1") (pinfunction "GND_B1") (pintype "bidirectional"))
      (node (ref "U$30") (pin "B1") (pinfunction "GND_B1") (pintype "bidirectional"))
      (node (ref "U$48") (pin "B1") (pinfunction "GND_B1") (pintype "bidirectional"))
      (node (ref "U$5") (pin "B1") (pinfunction "GND_B1") (pintype "bidirectional"))
      (node (ref "U$60") (pin "B1") (pinfunction "GND_B1") (pintype "bidirectional"))
      (node (ref "U$62") (pin "B1") (pinfunction "GND_B1") (pintype "bidirectional"))
      (node (ref "U$99") (pin "B1") (pinfunction "GND_B1") (pintype "bidirectional"))
      (node (ref "U1") (pin "10") (pinfunction "GND1_10") (pintype "power_in"))
      (node (ref "U1") (pin "28") (pinfunction "GND2_28") (pintype "power_in"))
      (node (ref "U1") (pin "33") (pinfunction "GND_33") (pintype "power_in"))
      (node (ref "U2") (pin "18") (pinfunction "GND2_18") (pintype "power_in"))
      (node (ref "U2") (pin "5") (pinfunction "NC/GND_5") (pintype "bidirectional"))
      (node (ref "U2") (pin "PAD") (pinfunction "GND_PAD") (pintype "power_in"))
      (node (ref "U3") (pin "2") (pinfunction "GNDA_2") (pintype "bidirectional"))
      (node (ref "U3") (pin "3") (pinfunction "GNDB_3") (pintype "bidirectional"))
      (node (ref "U3") (pin "5") (pinfunction "PGND_5") (pintype "bidirectional"))
      (node (ref "U3") (pin "PAD") (pinfunction "GND_PAD_PAD") (pintype "bidirectional"))
      (node (ref "U4") (pin "14_GND") (pinfunction "GND3_14_GND") (pintype "power_in"))
      (node (ref "U4") (pin "17_GND") (pinfunction "GND4_17_GND") (pintype "power_in"))
      (node (ref "U4") (pin "21_GND") (pinfunction "GND5_21_GND") (pintype "bidirectional"))
      (node (ref "U4") (pin "24_GND") (pinfunction "GND6_24_GND") (pintype "bidirectional"))
      (node (ref "U4") (pin "26_GND") (pinfunction "GND7_26_GND") (pintype "power_in"))
      (node (ref "U4") (pin "28_GND") (pinfunction "GND8_28_GND") (pintype "power_in"))
      (node (ref "U4") (pin "2_GND") (pinfunction "GND1_2_GND") (pintype "power_in"))
      (node (ref "U4") (pin "32_VDD_USB") (pinfunction "VDD_USB_32_VDD_USB") (pintype "bidirectional"))
      (node (ref "U4") (pin "33_GND") (pinfunction "GND9_33_GND") (pintype "power_in"))
      (node (ref "U4") (pin "34_GND") (pinfunction "GND10_34_GND") (pintype "power_in"))
      (node (ref "U4") (pin "35_GND") (pinfunction "GND11_35_GND") (pintype "bidirectional"))
      (node (ref "U4") (pin "36_GND") (pinfunction "GND12_36_GND") (pintype "bidirectional"))
      (node (ref "U4") (pin "4_GND") (pinfunction "GND2_4_GND") (pintype "power_in"))
      (node (ref "U5") (pin "4") (pinfunction "VSS_4") (pintype "power_in"))
      (node (ref "U5") (pin "PAD") (pinfunction "GND_PAD_PAD") (pintype "power_in"))
      (node (ref "U6") (pin "23") (pinfunction "VSS_23") (pintype "bidirectional"))
      (node (ref "U6") (pin "35") (pinfunction "VSS_35") (pintype "bidirectional"))
      (node (ref "U6") (pin "47") (pinfunction "VSS_47") (pintype "bidirectional"))
      (node (ref "U6") (pin "8") (pinfunction "VSSA_8") (pintype "bidirectional"))
      (node (ref "U7") (pin "3") (pinfunction "GND_3") (pintype "passive"))
      (node (ref "U7") (pin "6") (pinfunction "DAP_6") (pintype "passive"))
    )
    (net (code "56") (name "Net-(C1-P$1)") (class "Default")
      (node (ref "C1") (pin "1") (pinfunction "P$1_1") (pintype "passive"))
      (node (ref "U4") (pin "3_ANT_OUT") (pinfunction "ANT_OUT_3_ANT_OUT") (pintype "output"))
    )
    (net (code "57") (name "Net-(C1-P$2)") (class "Default")
      (node (ref "C1") (pin "2") (pinfunction "P$2_2") (pintype "passive"))
      (node (ref "U4") (pin "1_ANT_IN") (pinfunction "ANT_IN_1_ANT_IN") (pintype "input"))
    )
    (net (code "58") (name "Net-(C2-P$1)") (class "Default")
      (node (ref "C2") (pin "1") (pinfunction "P$1_1") (pintype "passive"))
      (node (ref "U1") (pin "29") (pinfunction "VDD_CORE_29") (pintype "power_in"))
    )
    (net (code "59") (name "Net-(C7-P$1)") (class "Default")
      (node (ref "C7") (pin "1") (pinfunction "P$1_1") (pintype "passive"))
      (node (ref "L3") (pin "2") (pinfunction "2_2") (pintype "passive"))
    )
    (net (code "60") (name "Net-(C7-P$2)") (class "Default")
      (node (ref "C7") (pin "2") (pinfunction "P$2_2") (pintype "passive"))
      (node (ref "L2") (pin "1") (pinfunction "1_1") (pintype "passive"))
      (node (ref "U2") (pin "4") (pinfunction "TX_4") (pintype "output"))
    )
    (net (code "61") (name "Net-(C8-P$1)") (class "Default")
      (node (ref "C8") (pin "1") (pinfunction "P$1_1") (pintype "passive"))
      (node (ref "L3") (pin "1") (pinfunction "1_1") (pintype "passive"))
      (node (ref "L4") (pin "2") (pinfunction "2_2") (pintype "passive"))
    )
    (net (code "62") (name "Net-(C9-P$1)") (class "Default")
      (node (ref "C9") (pin "1") (pinfunction "P$1_1") (pintype "passive"))
      (node (ref "L4") (pin "1") (pinfunction "1_1") (pintype "passive"))
      (node (ref "L5") (pin "2") (pinfunction "2_2") (pintype "passive"))
    )
    (net (code "63") (name "Net-(C15-P$1)") (class "Default")
      (node (ref "C15") (pin "1") (pinfunction "P$1_1") (pintype "passive"))
      (node (ref "R4") (pin "1") (pinfunction "1_1") (pintype "passive"))
      (node (ref "U4") (pin "13_RX") (pinfunction "RX_13_RX") (pintype "bidirectional"))
    )
    (net (code "64") (name "Net-(CN1-PadD+)") (class "Default")
      (node (ref "CN1") (pin "D+") (pinfunction "D+_D+") (pintype "bidirectional"))
      (node (ref "R12") (pin "2") (pinfunction "2_2") (pintype "passive"))
      (node (ref "R21") (pin "2") (pinfunction "2_2") (pintype "passive"))
    )
    (net (code "65") (name "Net-(CN1-PadD-)") (class "Default")
      (node (ref "CN1") (pin "D-") (pinfunction "D-_D-") (pintype "bidirectional"))
      (node (ref "R19") (pin "2") (pinfunction "2_2") (pintype "passive"))
    )
    (net (code "66") (name "Net-(D1-PadC)") (class "Default")
      (node (ref "D1") (pin "C") (pinfunction "C_C") (pintype "passive"))
      (node (ref "R1") (pin "2") (pinfunction "2_2") (pintype "passive"))
    )
    (net (code "67") (name "Net-(D2-PadA)") (class "Default")
      (node (ref "D2") (pin "A") (pinfunction "A_A") (pintype "passive"))
      (node (ref "R25") (pin "2") (pinfunction "2_2") (pintype "passive"))
    )
    (net (code "68") (name "Net-(D3-PadA)") (class "Default")
      (node (ref "D3") (pin "A") (pinfunction "A_A") (pintype "passive"))
      (node (ref "R26") (pin "2") (pinfunction "2_2") (pintype "passive"))
    )
    (net (code "69") (name "Net-(D4-PadA)") (class "Default")
      (node (ref "D4") (pin "A") (pinfunction "A_A") (pintype "passive"))
      (node (ref "R27") (pin "2") (pinfunction "2_2") (pintype "passive"))
    )
    (net (code "70") (name "Net-(D5-PadA)") (class "Default")
      (node (ref "D5") (pin "A") (pinfunction "A_A") (pintype "passive"))
      (node (ref "R28") (pin "2") (pinfunction "2_2") (pintype "passive"))
    )
    (net (code "71") (name "Net-(U3-LX)") (class "Default")
      (node (ref "L1") (pin "1") (pinfunction "1_1") (pintype "passive"))
      (node (ref "U3") (pin "6") (pinfunction "LX_6") (pintype "bidirectional"))
    )
    (net (code "72") (name "Net-(U4-TIMEPULSE{slash}TDO)") (class "Default")
      (node (ref "R2") (pin "2") (pinfunction "2_2") (pintype "passive"))
      (node (ref "U4") (pin "23_TIMEPULSE/TDO") (pinfunction "TIMEPULSE/TDO_23_TIMEPULSE/TDO") (pintype "bidirectional"))
    )
    (net (code "73") (name "Net-(U4-TX)") (class "Default")
      (node (ref "R3") (pin "1") (pinfunction "1_1") (pintype "passive"))
      (node (ref "U4") (pin "11_TX") (pinfunction "TX_11_TX") (pintype "bidirectional"))
    )
    (net (code "74") (name "Net-(U6-BOOT0)") (class "Default")
      (node (ref "BTN1") (pin "1") (pinfunction "1_1") (pintype "bidirectional"))
      (node (ref "R29") (pin "2") (pinfunction "2_2") (pintype "passive"))
      (node (ref "U6") (pin "44") (pinfunction "BOOT0_44") (pintype "bidirectional"))
    )
    (net (code "75") (name "Net-(U6-PD0{slash}OSC_IN)") (class "Default")
      (node (ref "C20") (pin "2") (pinfunction "2_2") (pintype "passive"))
      (node (ref "U6") (pin "5") (pinfunction "PD0/OSC_IN_5") (pintype "bidirectional"))
      (node (ref "Y1") (pin "3") (pinfunction "2_3") (pintype "passive"))
    )
    (net (code "76") (name "Net-(U6-PD1{slash}OSC_OUT)") (class "Default")
      (node (ref "C21") (pin "2") (pinfunction "2_2") (pintype "passive"))
      (node (ref "U6") (pin "6") (pinfunction "PD1/OSC_OUT_6") (pintype "bidirectional"))
      (node (ref "Y1") (pin "1") (pinfunction "1_1") (pintype "passive"))
    )
    (net (code "77") (name "unconnected-(JTAG1-Pad6)") (class "Default")
      (node (ref "JTAG1") (pin "6") (pinfunction "6_6") (pintype "passive"))
    )
    (net (code "78") (name "unconnected-(JTAG1-Pad7)") (class "Default")
      (node (ref "JTAG1") (pin "7") (pinfunction "7_7") (pintype "passive"))
    )
    (net (code "79") (name "unconnected-(JTAG1-Pad8)") (class "Default")
      (node (ref "JTAG1") (pin "8") (pinfunction "8_8") (pintype "passive"))
    )
    (net (code "80") (name "unconnected-(JTAG1-Pad9)") (class "Default")
      (node (ref "JTAG1") (pin "9") (pinfunction "9_9") (pintype "passive"))
    )
    (net (code "81") (name "unconnected-(JTAG2-Pad6)") (class "Default")
      (node (ref "JTAG2") (pin "6") (pinfunction "6_6") (pintype "passive"))
    )
    (net (code "82") (name "unconnected-(JTAG2-Pad7)") (class "Default")
      (node (ref "JTAG2") (pin "7") (pinfunction "7_7") (pintype "passive"))
    )
    (net (code "83") (name "unconnected-(JTAG2-Pad8)") (class "Default")
      (node (ref "JTAG2") (pin "8") (pinfunction "8_8") (pintype "passive"))
    )
    (net (code "84") (name "unconnected-(JTAG2-Pad9)") (class "Default")
      (node (ref "JTAG2") (pin "9") (pinfunction "9_9") (pintype "passive"))
    )
    (net (code "85") (name "unconnected-(JTAG2-Pad10)") (class "Default")
      (node (ref "JTAG2") (pin "10") (pinfunction "10_10") (pintype "passive"))
    )
    (net (code "86") (name "unconnected-(U1-PA02-Pad3)") (class "Default")
      (node (ref "U1") (pin "3") (pinfunction "PA02_3") (pintype "bidirectional"))
    )
    (net (code "87") (name "unconnected-(U1-PA03-Pad4)") (class "Default")
      (node (ref "U1") (pin "4") (pinfunction "PA03_4") (pintype "bidirectional"))
    )
    (net (code "88") (name "unconnected-(U1-PA05-Pad6)") (class "Default")
      (node (ref "U1") (pin "6") (pinfunction "PA05_6") (pintype "bidirectional"))
    )
    (net (code "89") (name "unconnected-(U1-PA14-Pad15)") (class "Default")
      (node (ref "U1") (pin "15") (pinfunction "PA14_15") (pintype "bidirectional"))
    )
    (net (code "90") (name "unconnected-(U1-PA15-Pad16)") (class "Default")
      (node (ref "U1") (pin "16") (pinfunction "PA15_16") (pintype "bidirectional"))
    )
    (net (code "91") (name "unconnected-(U2-GPIO2-Pad19)") (class "Default")
      (node (ref "U2") (pin "19") (pinfunction "GPIO2_19") (pintype "bidirectional"))
    )
    (net (code "92") (name "unconnected-(U2-GPIO3-Pad20)") (class "Default")
      (node (ref "U2") (pin "20") (pinfunction "GPIO3_20") (pintype "bidirectional"))
    )
    (net (code "93") (name "unconnected-(U2-NC-Pad2)") (class "Default")
      (node (ref "U2") (pin "2") (pinfunction "NC_2") (pintype "no_connect"))
    )
    (net (code "94") (name "unconnected-(U2-NC -Pad3)") (class "Default")
      (node (ref "U2") (pin "3") (pinfunction "NC _3") (pintype "no_connect"))
    )
    (net (code "95") (name "unconnected-(U2-TXRAMP-Pad7)") (class "Default")
      (node (ref "U2") (pin "7") (pinfunction "TXRAMP_7") (pintype "bidirectional"))
    )
    (net (code "96") (name "unconnected-(U2-XOUT-Pad16)") (class "Default")
      (node (ref "U2") (pin "16") (pinfunction "XOUT_16") (pintype "output"))
    )
    (net (code "97") (name "unconnected-(U4-CFG-Pad31_CFG)") (class "Default")
      (node (ref "U4") (pin "31_CFG") (pinfunction "CFG_31_CFG") (pintype "bidirectional"))
    )
    (net (code "98") (name "unconnected-(U4-CFG_GPS0{slash}SCK-Pad9_CFG_GPS0_SCK)") (class "Default")
      (node (ref "U4") (pin "9_CFG_GPS0_SCK") (pinfunction "CFG_GPS0/SCK_9_CFG_GPS0_SCK") (pintype "bidirectional"))
    )
    (net (code "99") (name "unconnected-(U4-EXT_INTERRUPT-Pad29_EXT_INTERRUPT)") (class "Default")
      (node (ref "U4") (pin "29_EXT_INTERRUPT") (pinfunction "EXT_INTERRUPT_29_EXT_INTERRUPT") (pintype "bidirectional"))
    )
    (net (code "100") (name "unconnected-(U4-SAFEBOOT_N{slash}TDI-Pad20_SAFEBOOT_N{slash}TDI)") (class "Default")
      (node (ref "U4") (pin "20_SAFEBOOT_N/TDI") (pinfunction "SAFEBOOT_N/TDI_20_SAFEBOOT_N/TDI") (pintype "bidirectional"))
    )
    (net (code "101") (name "unconnected-(U4-SCL-Pad19_SCL)") (class "Default")
      (node (ref "U4") (pin "19_SCL") (pinfunction "SCL_19_SCL") (pintype "bidirectional"))
    )
    (net (code "102") (name "unconnected-(U4-SDA-Pad18_SDA)") (class "Default")
      (node (ref "U4") (pin "18_SDA") (pinfunction "SDA_18_SDA") (pintype "bidirectional"))
    )
    (net (code "103") (name "unconnected-(U4-SI-Pad16_SI)") (class "Default")
      (node (ref "U4") (pin "16_SI") (pinfunction "SI_16_SI") (pintype "bidirectional"))
    )
    (net (code "104") (name "unconnected-(U4-SO-Pad8_SO)") (class "Default")
      (node (ref "U4") (pin "8_SO") (pinfunction "SO_8_SO") (pintype "bidirectional"))
    )
    (net (code "105") (name "unconnected-(U4-SPI_CS-Pad10_SPI_SELECT)") (class "Default")
      (node (ref "U4") (pin "10_SPI_SELECT") (pinfunction "SPI_CS_10_SPI_SELECT") (pintype "bidirectional"))
    )
    (net (code "106") (name "unconnected-(U4-TCK-Pad22_TCK)") (class "Default")
      (node (ref "U4") (pin "22_TCK") (pinfunction "TCK_22_TCK") (pintype "bidirectional"))
    )
    (net (code "107") (name "unconnected-(U4-USB_DM-Pad7_USB_DM)") (class "Default")
      (node (ref "U4") (pin "7_USB_DM") (pinfunction "USB_DM_7_USB_DM") (pintype "bidirectional"))
    )
    (net (code "108") (name "unconnected-(U4-USB_DP-Pad6_USB_DP)") (class "Default")
      (node (ref "U4") (pin "6_USB_DP") (pinfunction "USB_DP_6_USB_DP") (pintype "bidirectional"))
    )
    (net (code "109") (name "unconnected-(U4-V_BCKP-Pad15_V_BCKUP)") (class "Default")
      (node (ref "U4") (pin "15_V_BCKUP") (pinfunction "V_BCKP_15_V_BCKUP") (pintype "bidirectional"))
    )
    (net (code "110") (name "unconnected-(U4-V_EN-Pad30_V_EN)") (class "Default")
      (node (ref "U4") (pin "30_V_EN") (pinfunction "V_EN_30_V_EN") (pintype "bidirectional"))
    )
    (net (code "111") (name "unconnected-(U4-V_TH-Pad12_V_TH)") (class "Default")
      (node (ref "U4") (pin "12_V_TH") (pinfunction "V_TH_12_V_TH") (pintype "bidirectional"))
    )
    (net (code "112") (name "unconnected-(U5-IO3{slash}RESETN-Pad7)") (class "Default")
      (node (ref "U5") (pin "7") (pinfunction "IO3/RESETN_7") (pintype "output"))
    )
    (net (code "113") (name "unconnected-(U6-NRST-Pad7)") (class "Default")
      (node (ref "U6") (pin "7") (pinfunction "NRST_7") (pintype "bidirectional"))
    )
    (net (code "114") (name "unconnected-(U6-PA9-Pad30)") (class "Default")
      (node (ref "U6") (pin "30") (pinfunction "PA9_30") (pintype "bidirectional"))
    )
    (net (code "115") (name "unconnected-(U6-PA10-Pad31)") (class "Default")
      (node (ref "U6") (pin "31") (pinfunction "PA10_31") (pintype "bidirectional"))
    )
    (net (code "116") (name "unconnected-(U6-PA15{slash}JTDI-Pad38)") (class "Default")
      (node (ref "U6") (pin "38") (pinfunction "PA15/JTDI_38") (pintype "bidirectional"))
    )
    (net (code "117") (name "unconnected-(U6-PB3{slash}JTDO-Pad39)") (class "Default")
      (node (ref "U6") (pin "39") (pinfunction "PB3/JTDO_39") (pintype "bidirectional"))
    )
    (net (code "118") (name "unconnected-(U6-PB5-Pad41)") (class "Default")
      (node (ref "U6") (pin "41") (pinfunction "PB5_41") (pintype "bidirectional"))
    )
    (net (code "119") (name "unconnected-(U6-PB6-Pad42)") (class "Default")
      (node (ref "U6") (pin "42") (pinfunction "PB6_42") (pintype "bidirectional"))
    )
    (net (code "120") (name "unconnected-(U6-PB7-Pad43)") (class "Default")
      (node (ref "U6") (pin "43") (pinfunction "PB7_43") (pintype "bidirectional"))
    )
    (net (code "121") (name "unconnected-(U6-PB8-Pad45)") (class "Default")
      (node (ref "U6") (pin "45") (pinfunction "PB8_45") (pintype "bidirectional"))
    )
    (net (code "122") (name "unconnected-(U6-PB9-Pad46)") (class "Default")
      (node (ref "U6") (pin "46") (pinfunction "PB9_46") (pintype "bidirectional"))
    )
    (net (code "123") (name "unconnected-(U6-PB12-Pad25)") (class "Default")
      (node (ref "U6") (pin "25") (pinfunction "PB12_25") (pintype "bidirectional"))
    )
    (net (code "124") (name "unconnected-(U6-PB14-Pad27)") (class "Default")
      (node (ref "U6") (pin "27") (pinfunction "PB14_27") (pintype "bidirectional"))
    )
    (net (code "125") (name "unconnected-(U6-PB15-Pad28)") (class "Default")
      (node (ref "U6") (pin "28") (pinfunction "PB15_28") (pintype "bidirectional"))
    )
    (net (code "126") (name "unconnected-(U6-PC13{slash}TAMPER_RTC-Pad2)") (class "Default")
      (node (ref "U6") (pin "2") (pinfunction "PC13/TAMPER_RTC_2") (pintype "bidirectional"))
    )
    (net (code "127") (name "unconnected-(U6-PC14{slash}OSC32_IN-Pad3)") (class "Default")
      (node (ref "U6") (pin "3") (pinfunction "PC14/OSC32_IN_3") (pintype "bidirectional"))
    )
    (net (code "128") (name "unconnected-(U6-PC15{slash}OSC32_OUT-Pad4)") (class "Default")
      (node (ref "U6") (pin "4") (pinfunction "PC15/OSC32_OUT_4") (pintype "bidirectional"))
    )
  )
)
